# Power_Management.net
KiCad netlist of a schematic drawn in Altium Designer
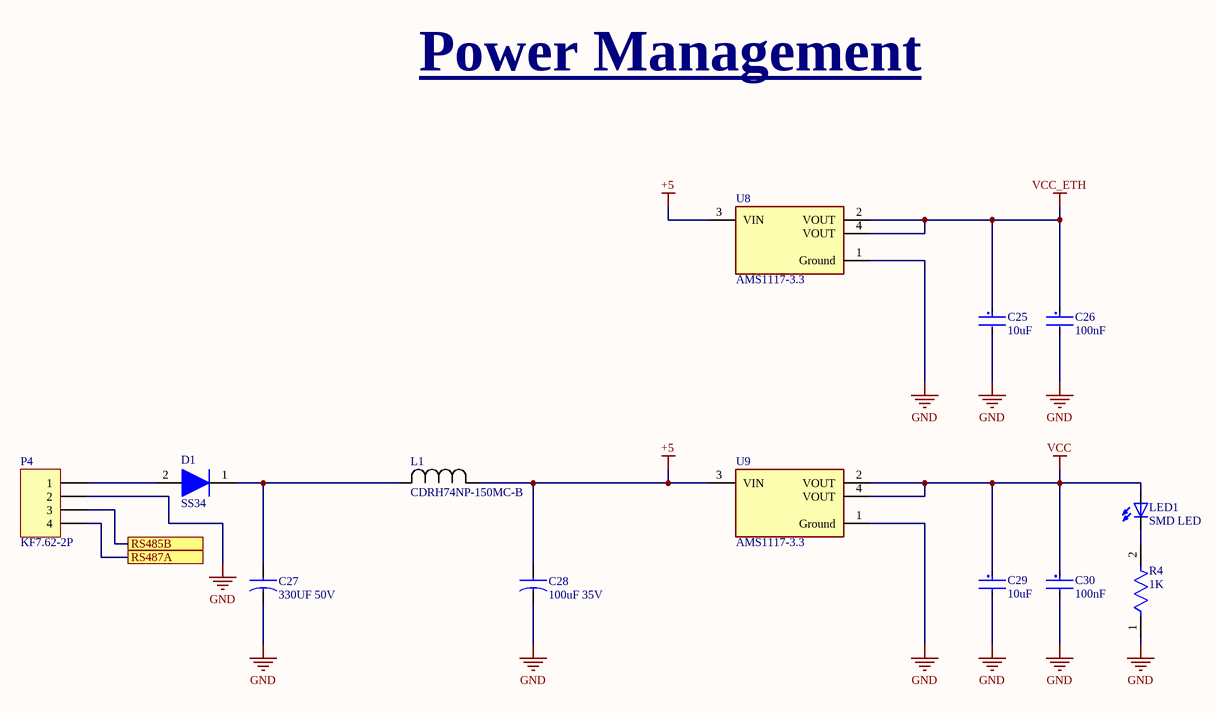
[diagram p0: Power_Management.SchDoc]

(export (version "E")
  (design (tool "Eeschema 10.0.6"))
  (components
    (comp (ref "C25")
      (value "10uF")
      (footprint "Samsung_CL31_IPC_A_1206")
      (description "CAP CER 10UF 6.3V X5R 1206, ±10% 6.3V Ceramic Capacitor X5R 1206 (3216 Metric)")
      (libsource (lib "DMD_Card") (part "CL31A106KQHNNWE"))
    )
    (comp (ref "C26")
      (value "100nF")
      (footprint "Samsung_CL31_IPC_A_1206")
      (description "CAP CER 0.1UF 50V X7R 1206, ±10% 50V Ceramic Capacitor X7R 1206 (3216 Metric)")
      (libsource (lib "DMD_Card") (part "CL31B104KBCNFNC"))
    )
    (comp (ref "C27")
      (value "330UF 50V")
      (footprint "CAP_PAN_EEE_D8_PAN")
      (description "Aluminum Electrolytic Capacitors Radial, Can - 10000 Hrs @ 105°C")
      (fields
        (field (name "MANUFACTURER") "Rubycon")
        (field (name "MANUFACTURER PART NUMBER") "50YXJ330M10X20")
      )
      (libsource (lib "DMD_Card") (part "330 uF 50 V Electrolytic Capacitors"))
    )
    (comp (ref "C28")
      (value "100uF 35V")
      (footprint "CAP_PAN_EEE_D8_PAN")
      (description "Aluminum Electrolytic Capacitors Radial, Can - 1000 Hrs @ 105°C")
      (fields
        (field (name "MANUFACTURER") "Panasonic")
        (field (name "MANUFACTURER PART NUMBER") "EEU-HD1V101")
      )
      (libsource (lib "DMD_Card") (part "100 uF 35 V Electrolytic Capacitors Radial"))
    )
    (comp (ref "C29")
      (value "10uF")
      (footprint "Samsung_CL31_IPC_A_1206")
      (description "CAP CER 10UF 6.3V X5R 1206, ±10% 6.3V Ceramic Capacitor X5R 1206 (3216 Metric)")
      (libsource (lib "DMD_Card") (part "CL31A106KQHNNWE"))
    )
    (comp (ref "C30")
      (value "100nF")
      (footprint "Samsung_CL31_IPC_A_1206")
      (description "CAP CER 0.1UF 50V X7R 1206, ±10% 50V Ceramic Capacitor X7R 1206 (3216 Metric)")
      (libsource (lib "DMD_Card") (part "CL31B104KBCNFNC"))
    )
    (comp (ref "D1")
      (value "SS34")
      (footprint "SMA (DO-214AC)")
      (description "Rectifier, 2-Pin Axial_Lead, Pb-Free, Tape and Reel")
      (fields (field (name "MANUFACTURER") "On Semiconductor") (field (name "PARTNUMBER") "1N5819RLG"))
      (libsource (lib "DMD_Card") (part "1N5819RLG"))
    )
    (comp (ref "L1")
      (value "CDRH74NP-150MC-B")
      (footprint "IND_CDRH74_SUM")
      (description "No Description Available")
      (fields (field (name "COPYRIGHT") "Copyright (C) 2022 Ultra Librarian. All rights reserved."))
      (libsource (lib "DMD_Card") (part "CDRH74NP-150MC-B"))
    )
    (comp (ref "LED1")
      (value "SMD LED")
      (footprint "1206_Inductor")
      (description "Green 569nm LED Indication - Discrete 1.9V Radial")
      (fields (field (name "MP") "TLLG4400") (field (name "DIGI-KEY_PART_NUMBER") "TLLG4400-AS12TR-ND"))
      (libsource (lib "DMD_Card") (part "TLLG4400"))
    )
    (comp (ref "P4")
      (value "KF7.62-2P")
      (footprint "KF6.5-4P Barrier Terminal Block")
      (libsource (lib "DMD_Card") (part "KF6.5-4P Barrier Terminal Block"))
    )
    (comp (ref "R4")
      (value "1K")
      (footprint "YAGEO_RC1206-0_65_IPC_A")
      (description "1 ±5% 0.25W, 1/4W Chip Resistor 1206 (3216 Metric) Moisture Resistant Thick Film")
      (libsource (lib "DMD_Card") (part "RC1206JR-071KL"))
    )
    (comp (ref "U8")
      (value "AMS1117-3.3")
      (footprint "Advanced_Monolithic_Systems_AMS1117_IPC_A")
      (description "Fixed 15V 3.3V 1.3V @ 800mA SOT-223 Dropout Regulators(LDO) RoHS")
      (libsource (lib "DMD_Card") (part "AMS1117-3.3"))
    )
    (comp (ref "U9")
      (value "AMS1117-3.3")
      (footprint "Advanced_Monolithic_Systems_AMS1117_IPC_A")
      (description "Fixed 15V 3.3V 1.3V @ 800mA SOT-223 Dropout Regulators(LDO) RoHS")
      (libsource (lib "DMD_Card") (part "AMS1117-3.3"))
    )
  )
  (nets
    (net (code "1") (name "+5") (class "Default")
      (node (ref "C28") (pin "1") (pinfunction "1_1") (pintype "passive"))
      (node (ref "L1") (pin "1") (pinfunction "1_1") (pintype "passive"))
      (node (ref "U8") (pin "3") (pinfunction "VIN_3") (pintype "power_in"))
      (node (ref "U9") (pin "3") (pinfunction "VIN_3") (pintype "power_in"))
    )
    (net (code "2") (name "/RS485B") (class "Default")
      (node (ref "P4") (pin "3") (pinfunction "3_3") (pintype "passive"))
    )
    (net (code "3") (name "/RS487A") (class "Default")
      (node (ref "P4") (pin "4") (pinfunction "4_4") (pintype "passive"))
    )
    (net (code "4") (name "GND") (class "Default")
      (node (ref "C25") (pin "2") (pinfunction "2_2") (pintype "passive"))
      (node (ref "C26") (pin "2") (pinfunction "2_2") (pintype "passive"))
      (node (ref "C27") (pin "2") (pinfunction "2_2") (pintype "passive"))
      (node (ref "C28") (pin "2") (pinfunction "2_2") (pintype "passive"))
      (node (ref "C29") (pin "2") (pinfunction "2_2") (pintype "passive"))
      (node (ref "C30") (pin "2") (pinfunction "2_2") (pintype "passive"))
      (node (ref "P4") (pin "2") (pinfunction "2_2") (pintype "passive"))
      (node (ref "R4") (pin "1") (pinfunction "1_1") (pintype "passive"))
      (node (ref "U8") (pin "1") (pinfunction "Ground_1") (pintype "power_in"))
      (node (ref "U9") (pin "1") (pinfunction "Ground_1") (pintype "power_in"))
    )
    (net (code "5") (name "Net-(D1-A)") (class "Default")
      (node (ref "D1") (pin "2") (pinfunction "A_2") (pintype "passive"))
      (node (ref "P4") (pin "1") (pinfunction "1_1") (pintype "passive"))
    )
    (net (code "6") (name "Net-(D1-K)") (class "Default")
      (node (ref "C27") (pin "1") (pinfunction "1_1") (pintype "passive"))
      (node (ref "D1") (pin "1") (pinfunction "K_1") (pintype "passive"))
      (node (ref "L1") (pin "2") (pinfunction "2_2") (pintype "passive"))
    )
    (net (code "7") (name "Net-(LED1-Pad2)") (class "Default")
      (node (ref "LED1") (pin "2") (pinfunction "2_2") (pintype "passive"))
      (node (ref "R4") (pin "2") (pinfunction "2_2") (pintype "passive"))
    )
    (net (code "8") (name "VCC") (class "Default")
      (node (ref "C29") (pin "1") (pinfunction "1_1") (pintype "passive"))
      (node (ref "C30") (pin "1") (pinfunction "1_1") (pintype "passive"))
      (node (ref "LED1") (pin "1") (pinfunction "1_1") (pintype "passive"))
      (node (ref "U9") (pin "2") (pinfunction "VOUT_2") (pintype "passive"))
      (node (ref "U9") (pin "4") (pinfunction "VOUT_4") (pintype "passive"))
    )
    (net (code "9") (name "VCC_ETH") (class "Default")
      (node (ref "C25") (pin "1") (pinfunction "1_1") (pintype "passive"))
      (node (ref "C26") (pin "1") (pinfunction "1_1") (pintype "passive"))
      (node (ref "U8") (pin "2") (pinfunction "VOUT_2") (pintype "passive"))
      (node (ref "U8") (pin "4") (pinfunction "VOUT_4") (pintype "passive"))
    )
  )
)
